# 01-PowerSupply.net
KiCad netlist of a schematic drawn in Altium Designer
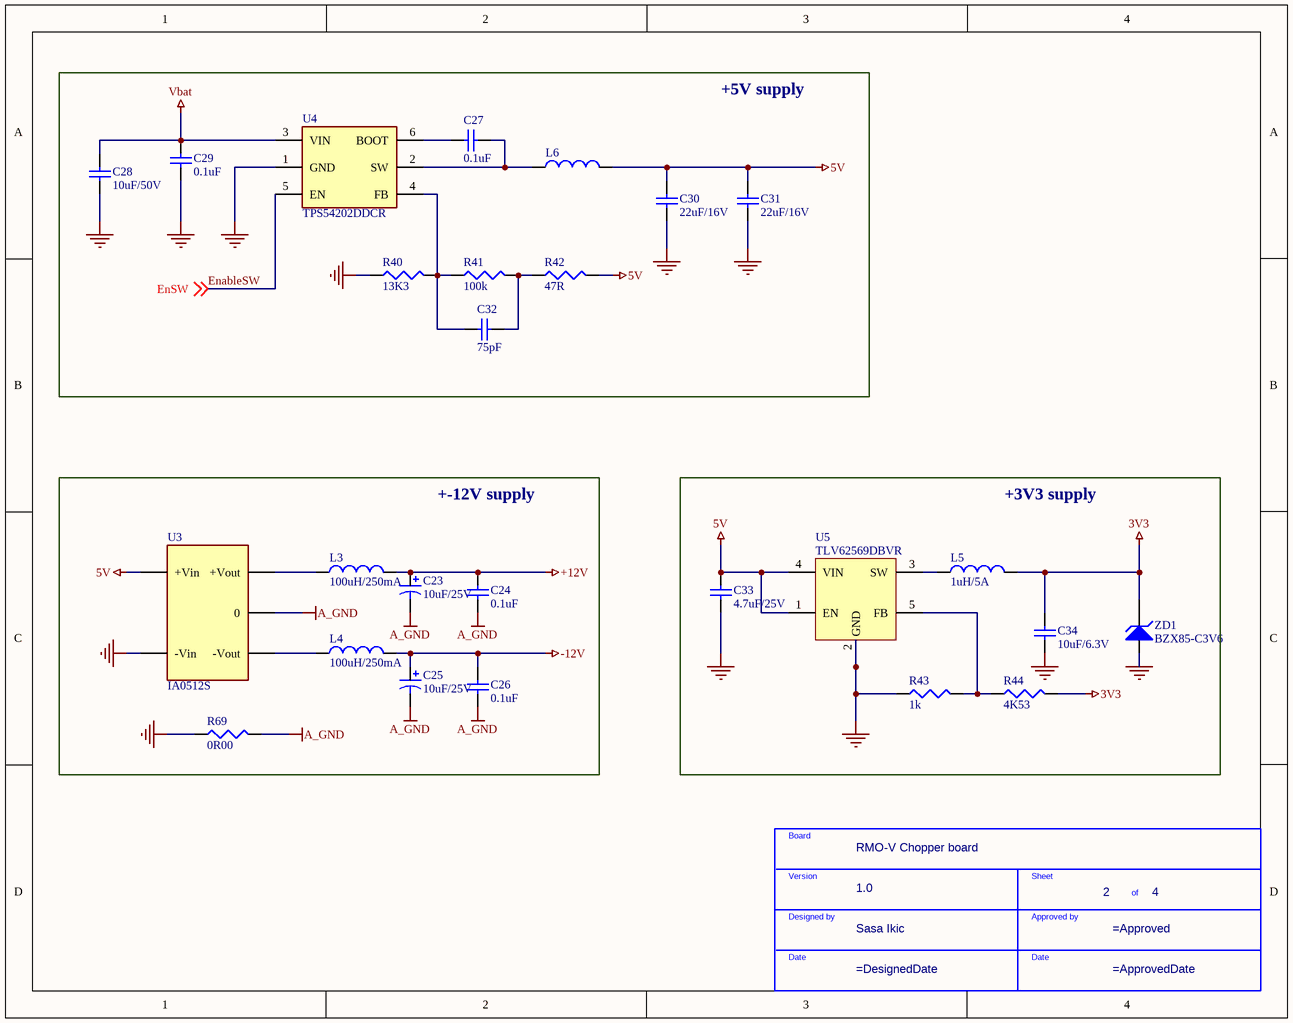
[diagram p0: 01-PowerSupply.SchDoc]

(export (version "E")
  (design (tool "Eeschema 10.0.6"))
  (components
    (comp (ref "C23")
      (value "10uF/25V")
      (footprint "CAPAED5.0x5.4")
      (description "CAP 10UF ELEC RAD 25V")
      (fields
        (field (name "MANUFACTURER") "Panasonic Electronic Components")
        (field (name "MANUFACTURER PART NUMBER") "EEE-1EA100SR")
        (field (name ".PCBCHECKED") "BP")
        (field (name ".SCHCHECKED") "BP")
      )
      (libsource (lib "My Library") (part "EEE-1EA100SR"))
    )
    (comp (ref "C24")
      (value "0.1uF")
      (footprint "C0805")
      (description "CAP 0.1uF 0805 50V")
      (fields
        (field (name "MANUFACTURER") "KEMET")
        (field (name "MANUFACTURER PART NUMBER") "08055C104KAT2A")
        (field (name ".PCBCHECKED") "BP")
        (field (name ".SCHCHECKED") "BP")
      )
      (libsource (lib "My Library") (part "08055C104KAT2A"))
    )
    (comp (ref "C25")
      (value "10uF/25V")
      (footprint "CAPAED5.0x5.4")
      (description "CAP 10UF ELEC RAD 25V")
      (fields
        (field (name "MANUFACTURER") "Panasonic Electronic Components")
        (field (name "MANUFACTURER PART NUMBER") "EEE-1EA100SR")
        (field (name ".PCBCHECKED") "BP")
        (field (name ".SCHCHECKED") "BP")
      )
      (libsource (lib "My Library") (part "EEE-1EA100SR"))
    )
    (comp (ref "C26")
      (value "0.1uF")
      (footprint "C0805")
      (description "CAP 0.1uF 0805 50V")
      (fields
        (field (name "MANUFACTURER") "KEMET")
        (field (name "MANUFACTURER PART NUMBER") "08055C104KAT2A")
        (field (name ".PCBCHECKED") "BP")
        (field (name ".SCHCHECKED") "BP")
      )
      (libsource (lib "My Library") (part "08055C104KAT2A"))
    )
    (comp (ref "C27")
      (value "0.1uF")
      (footprint "C0805")
      (description "CAP 0.1uF 0805 50V")
      (fields
        (field (name "MANUFACTURER") "KEMET")
        (field (name "MANUFACTURER PART NUMBER") "08055C104KAT2A")
        (field (name ".PCBCHECKED") "BP")
        (field (name ".SCHCHECKED") "BP")
      )
      (libsource (lib "My Library") (part "08055C104KAT2A"))
    )
    (comp (ref "C28")
      (value "10uF/50V")
      (footprint "CAPC3426X27N")
      (description "10µF ±20% 50V Ceramic Capacitor X7S 1210 (3225 Metric)")
      (fields
        (field (name "MANUFACTURER") "Taiyo Yuden")
        (field (name "MANUFACTURER PART NUMBER") "UMK325C7106MM-T")
      )
      (libsource (lib "RMOV_chopper") (part "UMK325C7106MM-T_1"))
    )
    (comp (ref "C29")
      (value "0.1uF")
      (footprint "C0805")
      (description "CAP 0.1uF 0805 50V")
      (fields
        (field (name "MANUFACTURER") "KEMET")
        (field (name "MANUFACTURER PART NUMBER") "08055C104KAT2A")
        (field (name ".PCBCHECKED") "BP")
        (field (name ".SCHCHECKED") "BP")
      )
      (libsource (lib "My Library") (part "08055C104KAT2A"))
    )
    (comp (ref "C30")
      (value "22uF/16V")
      (footprint "CAPC3426X27N")
      (description "Multilayer Ceramic Capacitors MLCC - SMD/SMT 1210 22uF 16volts *Derate Voltage/Temp")
      (fields
        (field (name "MANUFACTURER") "Murata")
        (field (name "MANUFACTURER PART NUMBER") "GRM32NC81C226KE15L")
      )
      (libsource (lib "RMOV_chopper") (part "GRM32NC81C226KE15L"))
    )
    (comp (ref "C31")
      (value "22uF/16V")
      (footprint "CAPC3426X27N")
      (description "Multilayer Ceramic Capacitors MLCC - SMD/SMT 1210 22uF 16volts *Derate Voltage/Temp")
      (fields
        (field (name "MANUFACTURER") "Murata")
        (field (name "MANUFACTURER PART NUMBER") "GRM32NC81C226KE15L")
      )
      (libsource (lib "RMOV_chopper") (part "GRM32NC81C226KE15L"))
    )
    (comp (ref "C32")
      (value "75pF")
      (footprint "C0805")
      (description "CAP 75PF 0805 50V")
      (fields
        (field (name "MANUFACTURER") "Yageo")
        (field (name "MANUFACTURER PART NUMBER") "CC0805JRNPO9BN750")
      )
      (libsource (lib "My Library") (part "CC0805JRNPO9BN750"))
    )
    (comp (ref "C33")
      (value "4.7uF/25V")
      (footprint "C0805")
      (description "CAP 4.7UF 0805 25V")
      (fields
        (field (name "MANUFACTURER") "Samsung")
        (field (name "MANUFACTURER PART NUMBER") "CL21A475KAQNNNE")
      )
      (libsource (lib "My Library") (part "CL21A475KAQNNNE"))
    )
    (comp (ref "C34")
      (value "10uF/6.3V")
      (footprint "C0805")
      (description "CAP 10UF 0805 6.3V")
      (fields
        (field (name "MANUFACTURER") "Taiyo Yuden")
        (field (name "MANUFACTURER PART NUMBER") "JMK212BJ106KD-T")
      )
      (libsource (lib "My Library") (part "JMK212BJ106KD-T"))
    )
    (comp (ref "L3")
      (value "100uH/250mA")
      (footprint "L1210")
      (description "IND 100UH 1210 250mA")
      (fields
        (field (name "MANUFACTURER") "Taiyo Yuden")
        (field (name "MANUFACTURER PART NUMBER") "BRL3225T101K")
      )
      (libsource (lib "My Library") (part "BRL3225T101K"))
    )
    (comp (ref "L4")
      (value "100uH/250mA")
      (footprint "L1210")
      (description "IND 100UH 1210 250mA")
      (fields
        (field (name "MANUFACTURER") "Taiyo Yuden")
        (field (name "MANUFACTURER PART NUMBER") "BRL3225T101K")
      )
      (libsource (lib "My Library") (part "BRL3225T101K"))
    )
    (comp (ref "L5")
      (value "1uH/5A")
      (footprint "I1212")
      (description "IND 1UH 5A 24mOhm")
      (fields
        (field (name "MANUFACTURER") "Vishay Dale")
        (field (name "MANUFACTURER PART NUMBER") "IHLP1212BZER1R0M11")
      )
      (libsource (lib "My Library") (part "IHLP1212BZER1R0M11"))
    )
    (comp (ref "L6")
      (value "NR10050T220M")
      (footprint "INDP102100X52N")
      (description "FIXED IND 22UH 2.5A 58.5 MOHM")
      (fields (field (name "MANUFACTURER") "Taiyo Yuden") (field (name "TOLERANCE") "20%"))
      (libsource (lib "RMOV_chopper") (part "NR10050T220M"))
    )
    (comp (ref "R40")
      (value "13K3")
      (footprint "R0805")
      (description "RES 13K3 0805 0.125W 0.1%")
      (fields
        (field (name "MANUFACTURER") "Vishay Dale")
        (field (name "MANUFACTURER PART NUMBER") "TNPW080513K3BEEN")
      )
      (libsource (lib "My Library") (part "TNPW080513K3BEEN"))
    )
    (comp (ref "R41")
      (value "100k")
      (footprint "R0805")
      (description "RES 100K 0805 0.125W 1%")
      (fields
        (field (name "MANUFACTURER") "Vishay")
        (field (name "MANUFACTURER PART NUMBER") "CRCW0805100KFKEA")
      )
      (libsource (lib "My Library") (part "CRCW0805100KFKEA"))
    )
    (comp (ref "R42")
      (value "47R")
      (footprint "R0805")
      (description "RC Series 0805 0.125 W 47 Ohm ±1% ±100 ppm/°C SMT Thick Film Chip Resistor")
      (fields
        (field (name "MANUFACTURER") "Yageo")
        (field (name "MANUFACTURER PART NUMBER") "RC0805FR-0747RL")
      )
      (libsource (lib "RMOV_chopper") (part "RC0805FR-0747RL"))
    )
    (comp (ref "R43")
      (value "1k")
      (footprint "R0805")
      (description "RES 1K 0805 0.125W 1%")
      (fields
        (field (name "MANUFACTURER") "Vishay Dale")
        (field (name "MANUFACTURER PART NUMBER") "CRCW08051K00FKEA")
        (field (name ".PCBCHECKED") "BP")
        (field (name ".SCHCHECKED") "BP")
      )
      (libsource (lib "My Library") (part "CRCW08051K00FKEA"))
    )
    (comp (ref "R44")
      (value "4K53")
      (footprint "R0805")
      (description "RES 4K53 0805 0.125W 1%")
      (fields
        (field (name "MANUFACTURER") "Vishay")
        (field (name "MANUFACTURER PART NUMBER") "CRCW08054K53FKEA")
      )
      (libsource (lib "My Library") (part "CRCW08054K53FKEA"))
    )
    (comp (ref "R69")
      (value "0R00")
      (footprint "R0805")
      (description "Res Thick Film 0805 0 Ohm Jumper Molded SMD Paper T/R")
      (fields
        (field (name "MANUFACTURER") "Yageo")
        (field (name "MANUFACTURER PART NUMBER") "RC0805FR-070RL")
      )
      (libsource (lib "RMOV_chopper") (part "RC0805FR-070RL"))
    )
    (comp (ref "U3")
      (value "IA0512S")
      (footprint "SIP5")
      (description "DC/DC 5V +/-12V SIP5 1W")
      (fields (field (name "MANUFACTURER") "XP Power"))
      (libsource (lib "My Library") (part "IA0512S"))
    )
    (comp (ref "U4")
      (value "TPS54202DDCR")
      (footprint "SOT23-6")
      (description "IC REG BUCK ADJ 2A SYNC SOT23-6")
      (fields (field (name "MANUFACTURER") "Texas Instruments"))
      (libsource (lib "My Library") (part "TPS54202DDCR"))
    )
    (comp (ref "U5")
      (value "TLV62569DBVR")
      (footprint "SOT23-5")
      (description "IC REG BUCK ADJ 2A SOT23-5")
      (fields (field (name "MANUFACTURER") "Texas Instruments"))
      (libsource (lib "My Library") (part "TLV62569DBVR"))
    )
    (comp (ref "ZD1")
      (value "BZX85-C3V6")
      (footprint "SOD123")
      (description "ZENER 3.6V SOD123 1.3W")
      (fields
        (field (name "MANUFACTURER") "NEXPERIA")
        (field (name ".PCBCHECKED") "BP")
        (field (name ".SCHCHECKED") "BP")
      )
      (libsource (lib "My Library") (part "BZX85-C3V6"))
    )
  )
  (nets
    (net (code "1") (name "+12V") (class "Default")
      (node (ref "C23") (pin "1") (pinfunction "1_1") (pintype "passive"))
      (node (ref "C24") (pin "2") (pinfunction "20_2") (pintype "passive"))
      (node (ref "L3") (pin "2") (pinfunction "2_2") (pintype "passive"))
    )
    (net (code "2") (name "-12V") (class "Default")
      (node (ref "C25") (pin "1") (pinfunction "1_1") (pintype "passive"))
      (node (ref "C26") (pin "2") (pinfunction "20_2") (pintype "passive"))
      (node (ref "L4") (pin "2") (pinfunction "2_2") (pintype "passive"))
    )
    (net (code "3") (name "3V3") (class "Default")
      (node (ref "C34") (pin "2") (pinfunction "20_2") (pintype "passive"))
      (node (ref "L5") (pin "2") (pinfunction "2_2") (pintype "passive"))
      (node (ref "R44") (pin "2") (pinfunction "2_2") (pintype "passive"))
      (node (ref "ZD1") (pin "C") (pinfunction "C_C") (pintype "passive"))
    )
    (net (code "4") (name "5V") (class "Default")
      (node (ref "C30") (pin "2") (pinfunction "2_2") (pintype "passive"))
      (node (ref "C31") (pin "2") (pinfunction "2_2") (pintype "passive"))
      (node (ref "C33") (pin "2") (pinfunction "20_2") (pintype "passive"))
      (node (ref "L6") (pin "2") (pinfunction "2_2") (pintype "passive"))
      (node (ref "R42") (pin "2") (pinfunction "2_2") (pintype "passive"))
      (node (ref "U3") (pin "+Vin") (pinfunction "+Vin_+Vin") (pintype "passive"))
      (node (ref "U5") (pin "1") (pinfunction "EN_1") (pintype "passive"))
      (node (ref "U5") (pin "4") (pinfunction "VIN_4") (pintype "passive"))
    )
    (net (code "5") (name "A_GND") (class "Default")
      (node (ref "C23") (pin "2") (pinfunction "2_2") (pintype "passive"))
      (node (ref "C24") (pin "1") (pinfunction "1_1") (pintype "passive"))
      (node (ref "C25") (pin "2") (pinfunction "2_2") (pintype "passive"))
      (node (ref "C26") (pin "1") (pinfunction "1_1") (pintype "passive"))
      (node (ref "R69") (pin "2") (pinfunction "2_2") (pintype "passive"))
      (node (ref "U3") (pin "0") (pinfunction "0_0") (pintype "passive"))
    )
    (net (code "6") (name "EnSW") (class "Default")
      (node (ref "U4") (pin "5") (pinfunction "EN_5") (pintype "passive"))
    )
    (net (code "7") (name "Net-(C27-20)") (class "Default")
      (node (ref "C27") (pin "2") (pinfunction "20_2") (pintype "passive"))
      (node (ref "U4") (pin "6") (pinfunction "BOOT_6") (pintype "passive"))
    )
    (net (code "8") (name "Net-(C32-20)") (class "Default")
      (node (ref "C32") (pin "2") (pinfunction "20_2") (pintype "passive"))
      (node (ref "R41") (pin "2") (pinfunction "2_2") (pintype "passive"))
      (node (ref "R42") (pin "1") (pinfunction "1_1") (pintype "passive"))
    )
    (net (code "9") (name "Net-(L3-Pad1)") (class "Default")
      (node (ref "L3") (pin "1") (pinfunction "1_1") (pintype "passive"))
      (node (ref "U3") (pin "+Vout") (pinfunction "+Vout_+Vout") (pintype "passive"))
    )
    (net (code "10") (name "Net-(L4-Pad1)") (class "Default")
      (node (ref "L4") (pin "1") (pinfunction "1_1") (pintype "passive"))
      (node (ref "U3") (pin "-Vout") (pinfunction "-Vout_-Vout") (pintype "passive"))
    )
    (net (code "11") (name "Net-(U4-FB)") (class "Default")
      (node (ref "C32") (pin "1") (pinfunction "1_1") (pintype "passive"))
      (node (ref "R40") (pin "2") (pinfunction "2_2") (pintype "passive"))
      (node (ref "R41") (pin "1") (pinfunction "1_1") (pintype "passive"))
      (node (ref "U4") (pin "4") (pinfunction "FB_4") (pintype "passive"))
    )
    (net (code "12") (name "Net-(U4-SW)") (class "Default")
      (node (ref "C27") (pin "1") (pinfunction "1_1") (pintype "passive"))
      (node (ref "L6") (pin "1") (pinfunction "1_1") (pintype "passive"))
      (node (ref "U4") (pin "2") (pinfunction "SW_2") (pintype "passive"))
    )
    (net (code "13") (name "Net-(U5-FB)") (class "Default")
      (node (ref "R43") (pin "2") (pinfunction "2_2") (pintype "passive"))
      (node (ref "R44") (pin "1") (pinfunction "1_1") (pintype "passive"))
      (node (ref "U5") (pin "5") (pinfunction "FB_5") (pintype "passive"))
    )
    (net (code "14") (name "Net-(U5-SW)") (class "Default")
      (node (ref "L5") (pin "1") (pinfunction "1_1") (pintype "passive"))
      (node (ref "U5") (pin "3") (pinfunction "SW_3") (pintype "passive"))
    )
    (net (code "15") (name "P_GND") (class "Default")
      (node (ref "C28") (pin "1") (pinfunction "1_1") (pintype "passive"))
      (node (ref "C29") (pin "1") (pinfunction "1_1") (pintype "passive"))
      (node (ref "C30") (pin "1") (pinfunction "1_1") (pintype "passive"))
      (node (ref "C31") (pin "1") (pinfunction "1_1") (pintype "passive"))
      (node (ref "C33") (pin "1") (pinfunction "1_1") (pintype "passive"))
      (node (ref "C34") (pin "1") (pinfunction "1_1") (pintype "passive"))
      (node (ref "R40") (pin "1") (pinfunction "1_1") (pintype "passive"))
      (node (ref "R43") (pin "1") (pinfunction "1_1") (pintype "passive"))
      (node (ref "R69") (pin "1") (pinfunction "1_1") (pintype "passive"))
      (node (ref "U3") (pin "-Vin") (pinfunction "-Vin_-Vin") (pintype "passive"))
      (node (ref "U4") (pin "1") (pinfunction "GND_1") (pintype "passive"))
      (node (ref "U5") (pin "2") (pinfunction "GND_2") (pintype "passive"))
      (node (ref "ZD1") (pin "A") (pinfunction "A_A") (pintype "passive"))
    )
    (net (code "16") (name "Vbat") (class "Default")
      (node (ref "C28") (pin "2") (pinfunction "2_2") (pintype "passive"))
      (node (ref "C29") (pin "2") (pinfunction "20_2") (pintype "passive"))
      (node (ref "U4") (pin "3") (pinfunction "VIN_3") (pintype "passive"))
    )
  )
)
